# FFB_Arduino_Yoke_2_0_YokeBoard.net
KiCad netlist of a schematic drawn in EasyEDA
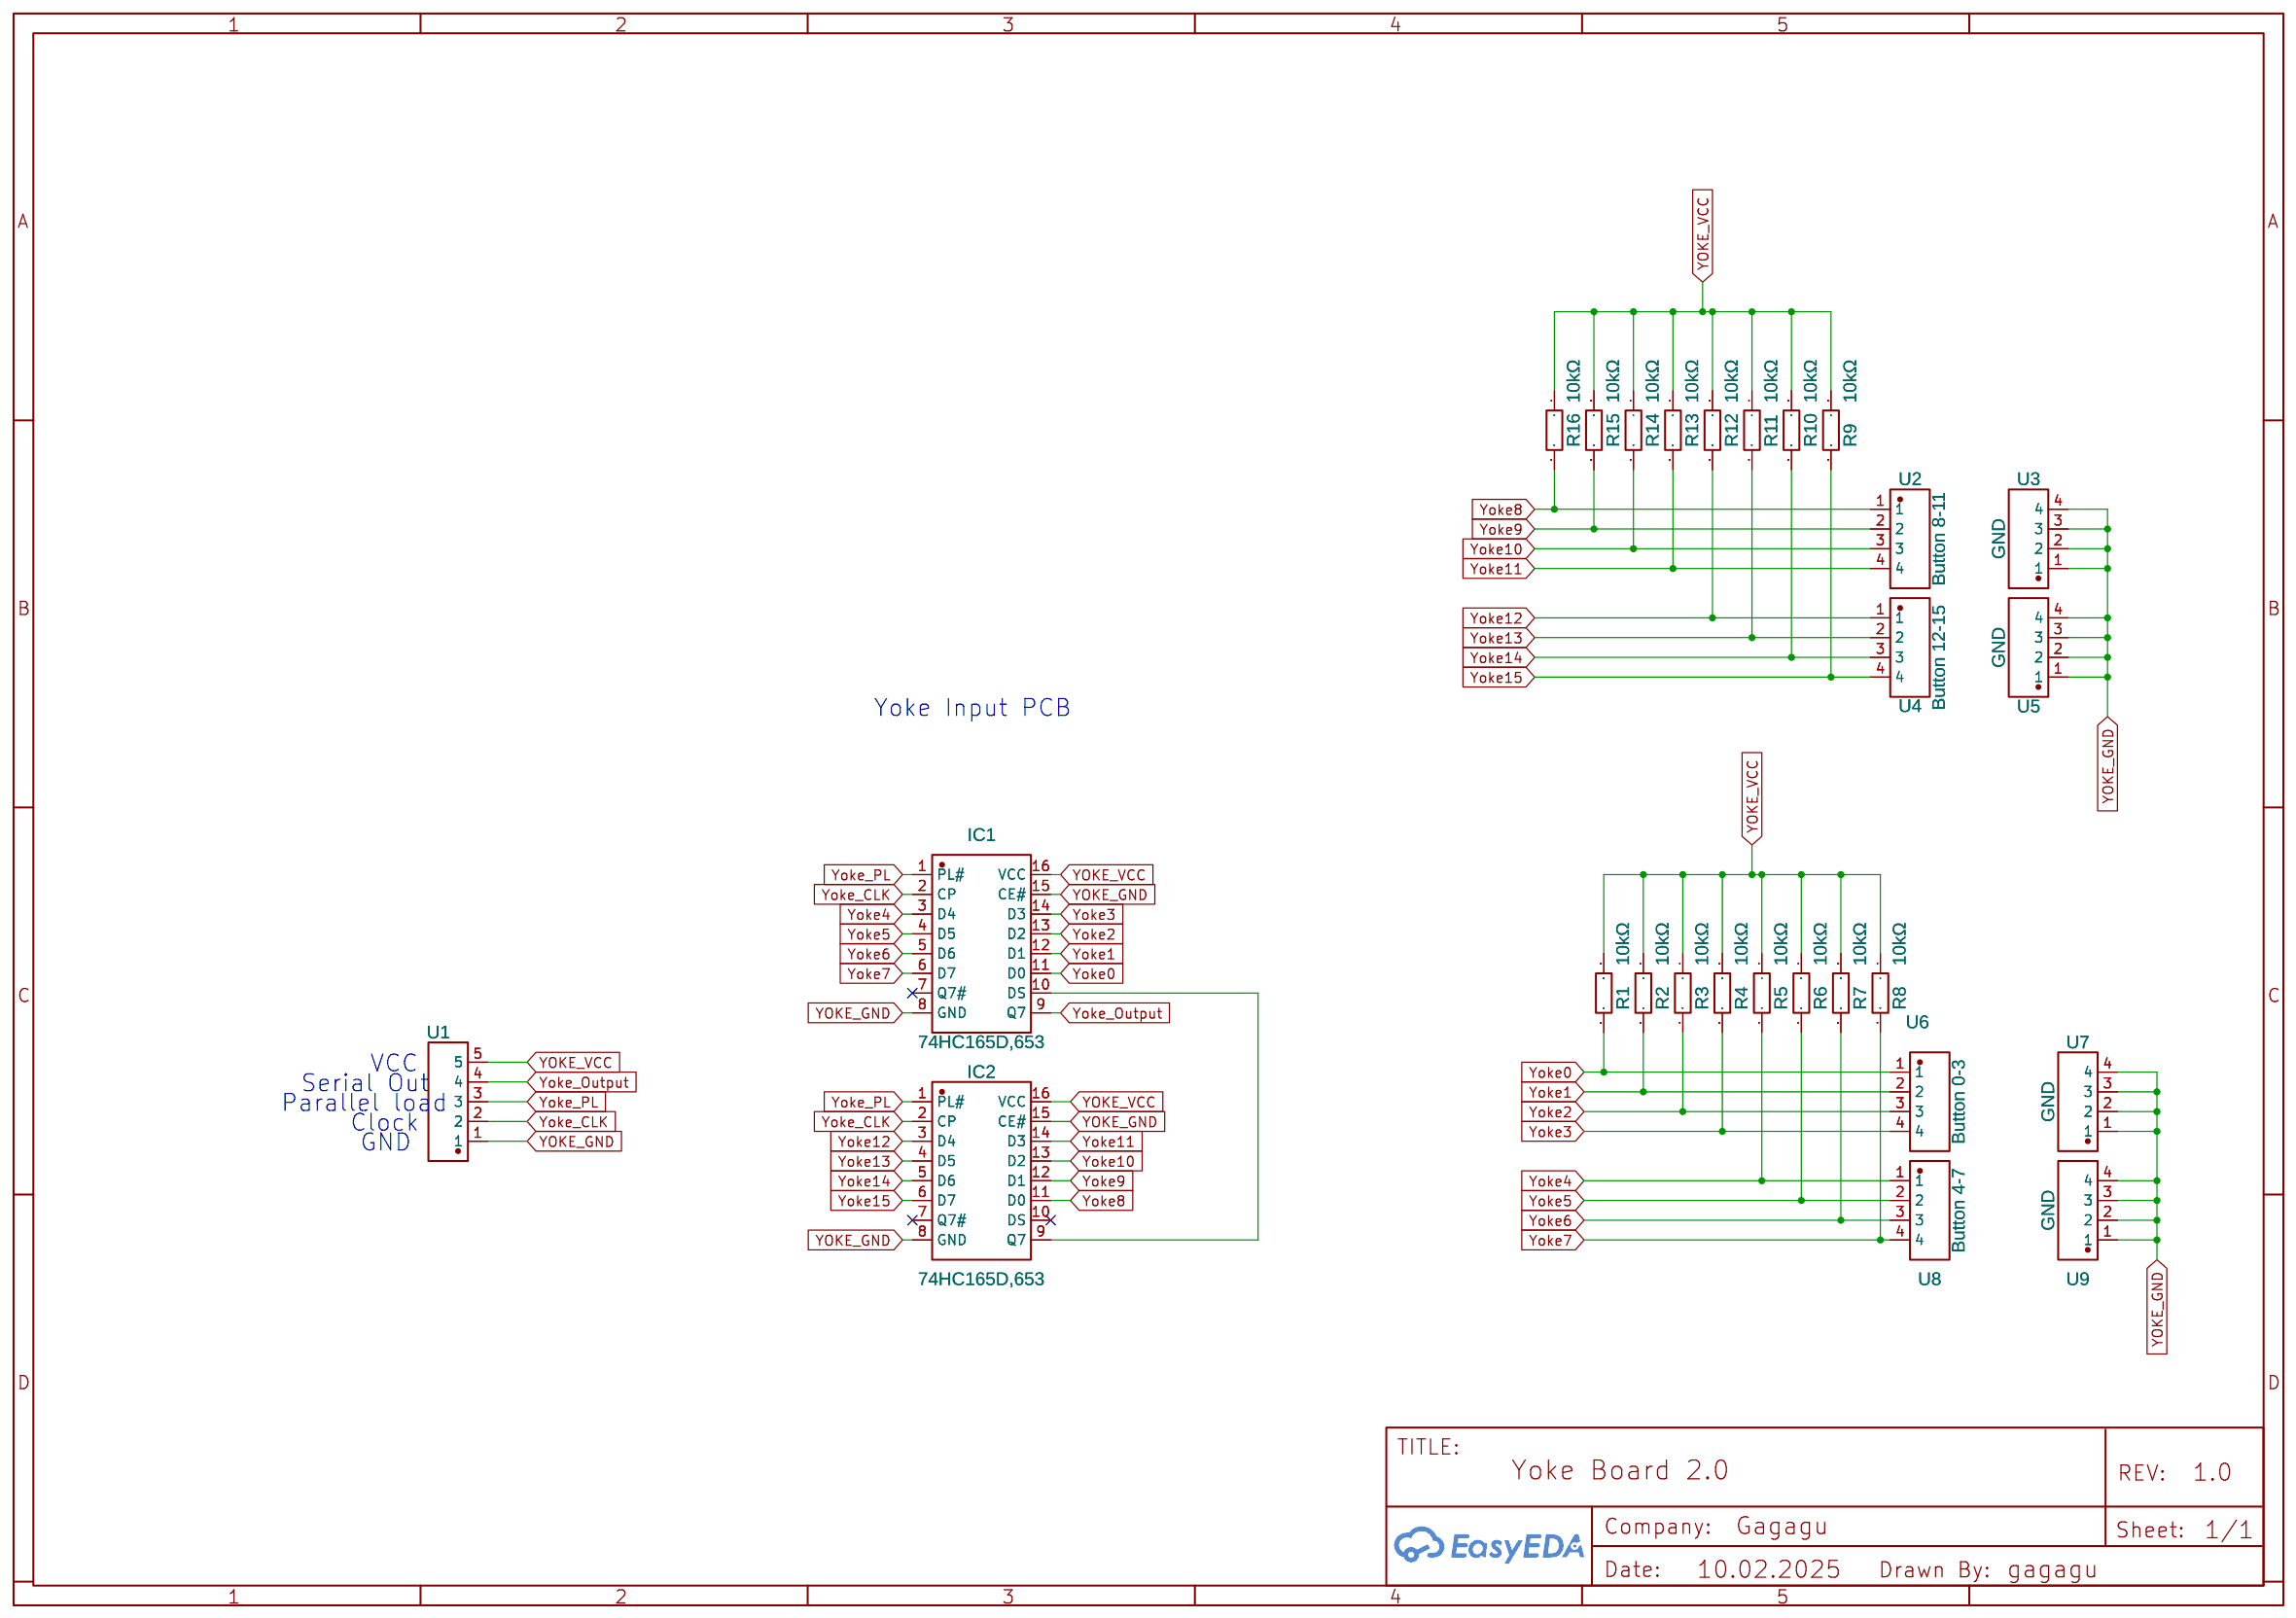
[diagram p0: schematic sheet]

(export (version "E")
  (design (tool "Eeschema 10.0.6"))
  (components
    (comp (ref "IC1")
      (value "74HC165D,653")
      (fields (field (name "Manufacturer") "Nexperia(安世)"))
      (libsource (lib "") (part "74HC165D,653"))
    )
    (comp (ref "IC2")
      (value "74HC165D,653")
      (fields (field (name "Manufacturer") "Nexperia(安世)"))
      (libsource (lib "") (part "74HC165D,653"))
    )
    (comp (ref "R1")
      (value "10kΩ")
      (fields
        (field (name "Manufacturer Part") "0603WAF1002T5E")
        (field (name "Manufacturer") "UNI-ROYAL(厚声)")
      )
      (libsource (lib "") (part "0603WAF1002T5E"))
    )
    (comp (ref "R2")
      (value "10kΩ")
      (fields
        (field (name "Manufacturer Part") "0603WAF1002T5E")
        (field (name "Manufacturer") "UNI-ROYAL(厚声)")
      )
      (libsource (lib "") (part "0603WAF1002T5E"))
    )
    (comp (ref "R3")
      (value "10kΩ")
      (fields
        (field (name "Manufacturer Part") "0603WAF1002T5E")
        (field (name "Manufacturer") "UNI-ROYAL(厚声)")
      )
      (libsource (lib "") (part "0603WAF1002T5E"))
    )
    (comp (ref "R4")
      (value "10kΩ")
      (fields
        (field (name "Manufacturer Part") "0603WAF1002T5E")
        (field (name "Manufacturer") "UNI-ROYAL(厚声)")
      )
      (libsource (lib "") (part "0603WAF1002T5E"))
    )
    (comp (ref "R5")
      (value "10kΩ")
      (fields
        (field (name "Manufacturer Part") "0603WAF1002T5E")
        (field (name "Manufacturer") "UNI-ROYAL(厚声)")
      )
      (libsource (lib "") (part "0603WAF1002T5E"))
    )
    (comp (ref "R6")
      (value "10kΩ")
      (fields
        (field (name "Manufacturer Part") "0603WAF1002T5E")
        (field (name "Manufacturer") "UNI-ROYAL(厚声)")
      )
      (libsource (lib "") (part "0603WAF1002T5E"))
    )
    (comp (ref "R7")
      (value "10kΩ")
      (fields
        (field (name "Manufacturer Part") "0603WAF1002T5E")
        (field (name "Manufacturer") "UNI-ROYAL(厚声)")
      )
      (libsource (lib "") (part "0603WAF1002T5E"))
    )
    (comp (ref "R8")
      (value "10kΩ")
      (fields
        (field (name "Manufacturer Part") "0603WAF1002T5E")
        (field (name "Manufacturer") "UNI-ROYAL(厚声)")
      )
      (libsource (lib "") (part "0603WAF1002T5E"))
    )
    (comp (ref "R9")
      (value "10kΩ")
      (fields
        (field (name "Manufacturer Part") "0603WAF1002T5E")
        (field (name "Manufacturer") "UNI-ROYAL(厚声)")
      )
      (libsource (lib "") (part "0603WAF1002T5E"))
    )
    (comp (ref "R10")
      (value "10kΩ")
      (fields
        (field (name "Manufacturer Part") "0603WAF1002T5E")
        (field (name "Manufacturer") "UNI-ROYAL(厚声)")
      )
      (libsource (lib "") (part "0603WAF1002T5E"))
    )
    (comp (ref "R11")
      (value "10kΩ")
      (fields
        (field (name "Manufacturer Part") "0603WAF1002T5E")
        (field (name "Manufacturer") "UNI-ROYAL(厚声)")
      )
      (libsource (lib "") (part "0603WAF1002T5E"))
    )
    (comp (ref "R12")
      (value "10kΩ")
      (fields
        (field (name "Manufacturer Part") "0603WAF1002T5E")
        (field (name "Manufacturer") "UNI-ROYAL(厚声)")
      )
      (libsource (lib "") (part "0603WAF1002T5E"))
    )
    (comp (ref "R13")
      (value "10kΩ")
      (fields
        (field (name "Manufacturer Part") "0603WAF1002T5E")
        (field (name "Manufacturer") "UNI-ROYAL(厚声)")
      )
      (libsource (lib "") (part "0603WAF1002T5E"))
    )
    (comp (ref "R14")
      (value "10kΩ")
      (fields
        (field (name "Manufacturer Part") "0603WAF1002T5E")
        (field (name "Manufacturer") "UNI-ROYAL(厚声)")
      )
      (libsource (lib "") (part "0603WAF1002T5E"))
    )
    (comp (ref "R15")
      (value "10kΩ")
      (fields
        (field (name "Manufacturer Part") "0603WAF1002T5E")
        (field (name "Manufacturer") "UNI-ROYAL(厚声)")
      )
      (libsource (lib "") (part "0603WAF1002T5E"))
    )
    (comp (ref "R16")
      (value "10kΩ")
      (fields
        (field (name "Manufacturer Part") "0603WAF1002T5E")
        (field (name "Manufacturer") "UNI-ROYAL(厚声)")
      )
      (libsource (lib "") (part "0603WAF1002T5E"))
    )
    (comp (ref "U1")
      (value "Yoke")
      (fields
        (field (name "Manufacturer Part") "MX128-2.54-05P-GN01-Cu-Y-A")
        (field (name "Manufacturer") "MAX(迈旭)")
      )
      (libsource (lib "") (part "MX128-2.54-05P-GN01-CU-Y-A"))
    )
    (comp (ref "U2")
      (value "Button 8-11")
      (fields
        (field (name "Manufacturer Part") "MX128-2.54-04P-GN01-Cu-Y-A")
        (field (name "Manufacturer") "MAX(迈旭)")
      )
      (libsource (lib "") (part "MX128-2.54-04P-GN01-CU-Y-A"))
    )
    (comp (ref "U3")
      (value "GND")
      (fields
        (field (name "Manufacturer Part") "MX128-2.54-04P-GN01-Cu-Y-A")
        (field (name "Manufacturer") "MAX(迈旭)")
      )
      (libsource (lib "") (part "MX128-2.54-04P-GN01-CU-Y-A_1"))
    )
    (comp (ref "U4")
      (value "Button 12-15")
      (fields
        (field (name "Manufacturer Part") "MX128-2.54-04P-GN01-Cu-Y-A")
        (field (name "Manufacturer") "MAX(迈旭)")
      )
      (libsource (lib "") (part "MX128-2.54-04P-GN01-CU-Y-A"))
    )
    (comp (ref "U5")
      (value "GND")
      (fields
        (field (name "Manufacturer Part") "MX128-2.54-04P-GN01-Cu-Y-A")
        (field (name "Manufacturer") "MAX(迈旭)")
      )
      (libsource (lib "") (part "MX128-2.54-04P-GN01-CU-Y-A_1"))
    )
    (comp (ref "U6")
      (value "Button 0-3")
      (fields
        (field (name "Manufacturer Part") "MX128-2.54-04P-GN01-Cu-Y-A")
        (field (name "Manufacturer") "MAX(迈旭)")
      )
      (libsource (lib "") (part "MX128-2.54-04P-GN01-CU-Y-A"))
    )
    (comp (ref "U7")
      (value "GND")
      (fields
        (field (name "Manufacturer Part") "MX128-2.54-04P-GN01-Cu-Y-A")
        (field (name "Manufacturer") "MAX(迈旭)")
      )
      (libsource (lib "") (part "MX128-2.54-04P-GN01-CU-Y-A_1"))
    )
    (comp (ref "U8")
      (value "Button 4-7")
      (fields
        (field (name "Manufacturer Part") "MX128-2.54-04P-GN01-Cu-Y-A")
        (field (name "Manufacturer") "MAX(迈旭)")
      )
      (libsource (lib "") (part "MX128-2.54-04P-GN01-CU-Y-A"))
    )
    (comp (ref "U9")
      (value "GND")
      (fields
        (field (name "Manufacturer Part") "MX128-2.54-04P-GN01-Cu-Y-A")
        (field (name "Manufacturer") "MAX(迈旭)")
      )
      (libsource (lib "") (part "MX128-2.54-04P-GN01-CU-Y-A_1"))
    )
  )
  (nets
    (net (code "1") (name "Net-(IC1-DS)") (class "Default")
      (node (ref "IC1") (pin "10") (pinfunction "DS_10") (pintype "unspecified"))
      (node (ref "IC2") (pin "9") (pinfunction "Q7_9") (pintype "unspecified"))
    )
    (net (code "2") (name "YOKE_GND") (class "Default")
      (node (ref "IC1") (pin "15") (pinfunction "CE#_15") (pintype "unspecified"))
      (node (ref "IC1") (pin "8") (pinfunction "GND_8") (pintype "unspecified"))
      (node (ref "IC2") (pin "15") (pinfunction "CE#_15") (pintype "unspecified"))
      (node (ref "IC2") (pin "8") (pinfunction "GND_8") (pintype "unspecified"))
      (node (ref "U1") (pin "1") (pinfunction "1_1") (pintype "unspecified"))
      (node (ref "U3") (pin "1") (pinfunction "1_1") (pintype "unspecified"))
      (node (ref "U3") (pin "2") (pinfunction "2_2") (pintype "unspecified"))
      (node (ref "U3") (pin "3") (pinfunction "3_3") (pintype "unspecified"))
      (node (ref "U3") (pin "4") (pinfunction "4_4") (pintype "unspecified"))
      (node (ref "U5") (pin "1") (pinfunction "1_1") (pintype "unspecified"))
      (node (ref "U5") (pin "2") (pinfunction "2_2") (pintype "unspecified"))
      (node (ref "U5") (pin "3") (pinfunction "3_3") (pintype "unspecified"))
      (node (ref "U5") (pin "4") (pinfunction "4_4") (pintype "unspecified"))
      (node (ref "U7") (pin "1") (pinfunction "1_1") (pintype "unspecified"))
      (node (ref "U7") (pin "2") (pinfunction "2_2") (pintype "unspecified"))
      (node (ref "U7") (pin "3") (pinfunction "3_3") (pintype "unspecified"))
      (node (ref "U7") (pin "4") (pinfunction "4_4") (pintype "unspecified"))
      (node (ref "U9") (pin "1") (pinfunction "1_1") (pintype "unspecified"))
      (node (ref "U9") (pin "2") (pinfunction "2_2") (pintype "unspecified"))
      (node (ref "U9") (pin "3") (pinfunction "3_3") (pintype "unspecified"))
      (node (ref "U9") (pin "4") (pinfunction "4_4") (pintype "unspecified"))
    )
    (net (code "3") (name "YOKE_VCC") (class "Default")
      (node (ref "IC1") (pin "16") (pinfunction "VCC_16") (pintype "unspecified"))
      (node (ref "IC2") (pin "16") (pinfunction "VCC_16") (pintype "unspecified"))
      (node (ref "R1") (pin "1") (pinfunction "1_1") (pintype "input"))
      (node (ref "R10") (pin "1") (pinfunction "1_1") (pintype "input"))
      (node (ref "R11") (pin "1") (pinfunction "1_1") (pintype "input"))
      (node (ref "R12") (pin "1") (pinfunction "1_1") (pintype "input"))
      (node (ref "R13") (pin "1") (pinfunction "1_1") (pintype "input"))
      (node (ref "R14") (pin "1") (pinfunction "1_1") (pintype "input"))
      (node (ref "R15") (pin "1") (pinfunction "1_1") (pintype "input"))
      (node (ref "R16") (pin "1") (pinfunction "1_1") (pintype "input"))
      (node (ref "R2") (pin "1") (pinfunction "1_1") (pintype "input"))
      (node (ref "R3") (pin "1") (pinfunction "1_1") (pintype "input"))
      (node (ref "R4") (pin "1") (pinfunction "1_1") (pintype "input"))
      (node (ref "R5") (pin "1") (pinfunction "1_1") (pintype "input"))
      (node (ref "R6") (pin "1") (pinfunction "1_1") (pintype "input"))
      (node (ref "R7") (pin "1") (pinfunction "1_1") (pintype "input"))
      (node (ref "R8") (pin "1") (pinfunction "1_1") (pintype "input"))
      (node (ref "R9") (pin "1") (pinfunction "1_1") (pintype "input"))
      (node (ref "U1") (pin "5") (pinfunction "5_5") (pintype "unspecified"))
    )
    (net (code "4") (name "Yoke0") (class "Default")
      (node (ref "IC1") (pin "11") (pinfunction "D0_11") (pintype "unspecified"))
      (node (ref "R1") (pin "2") (pinfunction "2_2") (pintype "input"))
      (node (ref "U6") (pin "1") (pinfunction "1_1") (pintype "unspecified"))
    )
    (net (code "5") (name "Yoke1") (class "Default")
      (node (ref "IC1") (pin "12") (pinfunction "D1_12") (pintype "unspecified"))
      (node (ref "R2") (pin "2") (pinfunction "2_2") (pintype "input"))
      (node (ref "U6") (pin "2") (pinfunction "2_2") (pintype "unspecified"))
    )
    (net (code "6") (name "Yoke2") (class "Default")
      (node (ref "IC1") (pin "13") (pinfunction "D2_13") (pintype "unspecified"))
      (node (ref "R3") (pin "2") (pinfunction "2_2") (pintype "input"))
      (node (ref "U6") (pin "3") (pinfunction "3_3") (pintype "unspecified"))
    )
    (net (code "7") (name "Yoke3") (class "Default")
      (node (ref "IC1") (pin "14") (pinfunction "D3_14") (pintype "unspecified"))
      (node (ref "R4") (pin "2") (pinfunction "2_2") (pintype "input"))
      (node (ref "U6") (pin "4") (pinfunction "4_4") (pintype "unspecified"))
    )
    (net (code "8") (name "Yoke4") (class "Default")
      (node (ref "IC1") (pin "3") (pinfunction "D4_3") (pintype "unspecified"))
      (node (ref "R5") (pin "2") (pinfunction "2_2") (pintype "input"))
      (node (ref "U8") (pin "1") (pinfunction "1_1") (pintype "unspecified"))
    )
    (net (code "9") (name "Yoke5") (class "Default")
      (node (ref "IC1") (pin "4") (pinfunction "D5_4") (pintype "unspecified"))
      (node (ref "R6") (pin "2") (pinfunction "2_2") (pintype "input"))
      (node (ref "U8") (pin "2") (pinfunction "2_2") (pintype "unspecified"))
    )
    (net (code "10") (name "Yoke6") (class "Default")
      (node (ref "IC1") (pin "5") (pinfunction "D6_5") (pintype "unspecified"))
      (node (ref "R7") (pin "2") (pinfunction "2_2") (pintype "input"))
      (node (ref "U8") (pin "3") (pinfunction "3_3") (pintype "unspecified"))
    )
    (net (code "11") (name "Yoke7") (class "Default")
      (node (ref "IC1") (pin "6") (pinfunction "D7_6") (pintype "unspecified"))
      (node (ref "R8") (pin "2") (pinfunction "2_2") (pintype "input"))
      (node (ref "U8") (pin "4") (pinfunction "4_4") (pintype "unspecified"))
    )
    (net (code "12") (name "Yoke8") (class "Default")
      (node (ref "IC2") (pin "11") (pinfunction "D0_11") (pintype "unspecified"))
      (node (ref "R16") (pin "2") (pinfunction "2_2") (pintype "input"))
      (node (ref "U2") (pin "1") (pinfunction "1_1") (pintype "unspecified"))
    )
    (net (code "13") (name "Yoke9") (class "Default")
      (node (ref "IC2") (pin "12") (pinfunction "D1_12") (pintype "unspecified"))
      (node (ref "R15") (pin "2") (pinfunction "2_2") (pintype "input"))
      (node (ref "U2") (pin "2") (pinfunction "2_2") (pintype "unspecified"))
    )
    (net (code "14") (name "Yoke10") (class "Default")
      (node (ref "IC2") (pin "13") (pinfunction "D2_13") (pintype "unspecified"))
      (node (ref "R14") (pin "2") (pinfunction "2_2") (pintype "input"))
      (node (ref "U2") (pin "3") (pinfunction "3_3") (pintype "unspecified"))
    )
    (net (code "15") (name "Yoke11") (class "Default")
      (node (ref "IC2") (pin "14") (pinfunction "D3_14") (pintype "unspecified"))
      (node (ref "R13") (pin "2") (pinfunction "2_2") (pintype "input"))
      (node (ref "U2") (pin "4") (pinfunction "4_4") (pintype "unspecified"))
    )
    (net (code "16") (name "Yoke12") (class "Default")
      (node (ref "IC2") (pin "3") (pinfunction "D4_3") (pintype "unspecified"))
      (node (ref "R12") (pin "2") (pinfunction "2_2") (pintype "input"))
      (node (ref "U4") (pin "1") (pinfunction "1_1") (pintype "unspecified"))
    )
    (net (code "17") (name "Yoke13") (class "Default")
      (node (ref "IC2") (pin "4") (pinfunction "D5_4") (pintype "unspecified"))
      (node (ref "R11") (pin "2") (pinfunction "2_2") (pintype "input"))
      (node (ref "U4") (pin "2") (pinfunction "2_2") (pintype "unspecified"))
    )
    (net (code "18") (name "Yoke14") (class "Default")
      (node (ref "IC2") (pin "5") (pinfunction "D6_5") (pintype "unspecified"))
      (node (ref "R10") (pin "2") (pinfunction "2_2") (pintype "input"))
      (node (ref "U4") (pin "3") (pinfunction "3_3") (pintype "unspecified"))
    )
    (net (code "19") (name "Yoke15") (class "Default")
      (node (ref "IC2") (pin "6") (pinfunction "D7_6") (pintype "unspecified"))
      (node (ref "R9") (pin "2") (pinfunction "2_2") (pintype "input"))
      (node (ref "U4") (pin "4") (pinfunction "4_4") (pintype "unspecified"))
    )
    (net (code "20") (name "Yoke_CLK") (class "Default")
      (node (ref "IC1") (pin "2") (pinfunction "CP_2") (pintype "unspecified"))
      (node (ref "IC2") (pin "2") (pinfunction "CP_2") (pintype "unspecified"))
      (node (ref "U1") (pin "2") (pinfunction "2_2") (pintype "unspecified"))
    )
    (net (code "21") (name "Yoke_Output") (class "Default")
      (node (ref "IC1") (pin "9") (pinfunction "Q7_9") (pintype "unspecified"))
      (node (ref "U1") (pin "4") (pinfunction "4_4") (pintype "unspecified"))
    )
    (net (code "22") (name "Yoke_PL") (class "Default")
      (node (ref "IC1") (pin "1") (pinfunction "PL#_1") (pintype "unspecified"))
      (node (ref "IC2") (pin "1") (pinfunction "PL#_1") (pintype "unspecified"))
      (node (ref "U1") (pin "3") (pinfunction "3_3") (pintype "unspecified"))
    )
    (net (code "23") (name "unconnected-(IC1-Q7#-Pad7)") (class "Default")
      (node (ref "IC1") (pin "7") (pinfunction "Q7#_7") (pintype "unspecified+no_connect"))
    )
    (net (code "24") (name "unconnected-(IC2-DS-Pad10)") (class "Default")
      (node (ref "IC2") (pin "10") (pinfunction "DS_10") (pintype "unspecified+no_connect"))
    )
    (net (code "25") (name "unconnected-(IC2-Q7#-Pad7)") (class "Default")
      (node (ref "IC2") (pin "7") (pinfunction "Q7#_7") (pintype "unspecified+no_connect"))
    )
  )
)
